# power_supply.net
KiCad netlist of a schematic drawn in Altium Designer
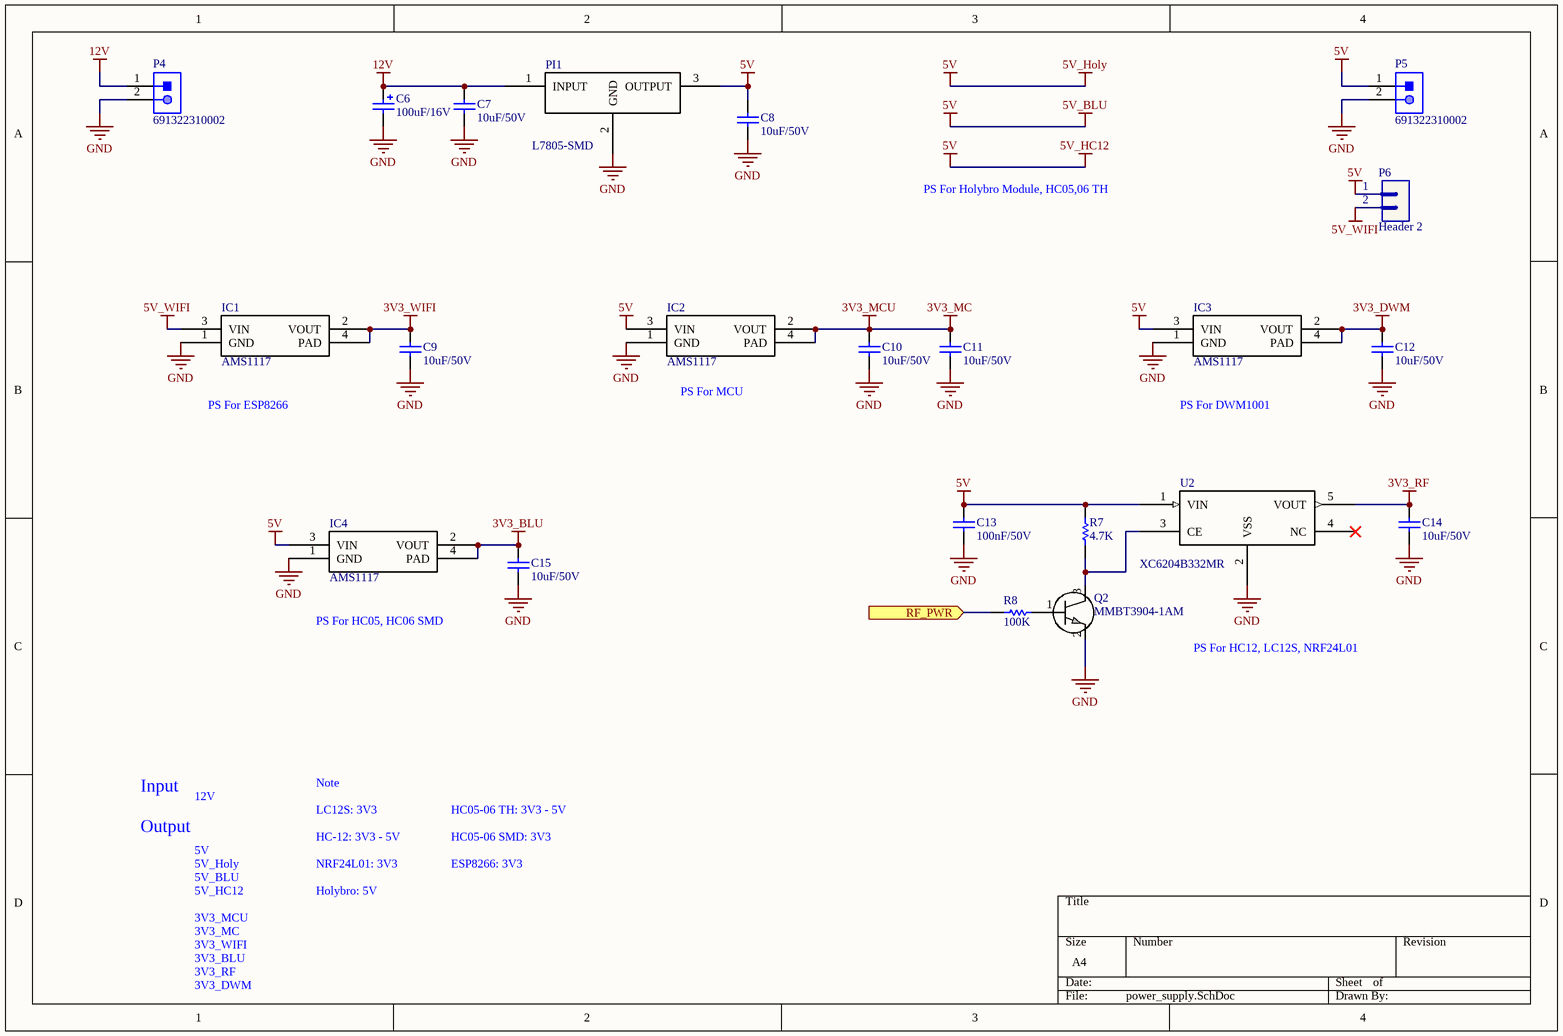
[diagram p0: power_supply.SchDoc]

(export (version "E")
  (design (tool "Eeschema 10.0.6"))
  (components
    (comp (ref "C6")
      (value "100uF/16V")
      (footprint "CAP-SM-AL-SIZE-D-D6L6")
      (description "CAP ALUM 100UF 20% 16V SMD")
      (fields
        (field (name "MANUFACTURER") "Nichicon")
        (field (name "MANUFACTURER PART NUMBER") "UWX1C101MCL1GB")
      )
      (libsource (lib "Capacitor") (part "Cap-Al-100uF-16V-D6L5"))
    )
    (comp (ref "C7")
      (value "10uF/50V")
      (footprint "CAP-SM-0805")
      (description "CAP CER 10UF 50V X5R 0805")
      (fields
        (field (name "MANUFACTURER") "Yageo")
        (field (name "MANUFACTURER PART NUMBER") "CC0805KKX5R9BB106")
      )
      (libsource (lib "Capacitor") (part "Cap-10uF-50V-0805"))
    )
    (comp (ref "C8")
      (value "10uF/50V")
      (footprint "CAP-SM-0805")
      (description "CAP CER 10UF 50V X5R 0805")
      (fields
        (field (name "MANUFACTURER") "Yageo")
        (field (name "MANUFACTURER PART NUMBER") "CC0805KKX5R9BB106")
      )
      (libsource (lib "Capacitor") (part "Cap-10uF-50V-0805"))
    )
    (comp (ref "C9")
      (value "10uF/50V")
      (footprint "CAP-SM-0805")
      (description "CAP CER 10UF 50V X5R 0805")
      (fields
        (field (name "MANUFACTURER") "Yageo")
        (field (name "MANUFACTURER PART NUMBER") "CC0805KKX5R9BB106")
      )
      (libsource (lib "Capacitor") (part "Cap-10uF-50V-0805"))
    )
    (comp (ref "C10")
      (value "10uF/50V")
      (footprint "CAP-SM-0805")
      (description "CAP CER 10UF 50V X5R 0805")
      (fields
        (field (name "MANUFACTURER") "Yageo")
        (field (name "MANUFACTURER PART NUMBER") "CC0805KKX5R9BB106")
      )
      (libsource (lib "Capacitor") (part "Cap-10uF-50V-0805"))
    )
    (comp (ref "C11")
      (value "10uF/50V")
      (footprint "CAP-SM-0805")
      (description "CAP CER 10UF 50V X5R 0805")
      (fields
        (field (name "MANUFACTURER") "Yageo")
        (field (name "MANUFACTURER PART NUMBER") "CC0805KKX5R9BB106")
      )
      (libsource (lib "Capacitor") (part "Cap-10uF-50V-0805"))
    )
    (comp (ref "C12")
      (value "10uF/50V")
      (footprint "CAP-SM-0805")
      (description "CAP CER 10UF 50V X5R 0805")
      (fields
        (field (name "MANUFACTURER") "Yageo")
        (field (name "MANUFACTURER PART NUMBER") "CC0805KKX5R9BB106")
      )
      (libsource (lib "Capacitor") (part "Cap-10uF-50V-0805"))
    )
    (comp (ref "C13")
      (value "100nF/50V")
      (footprint "CAP-SM-0805")
      (description "CAP CER 0.1UF 50V Y5V 0805")
      (fields
        (field (name "MANUFACTURER") "Samsung Electro-Mechanics")
        (field (name "MANUFACTURER PART NUMBER") "CL21F104ZBCNNNC")
      )
      (libsource (lib "Capacitor") (part "Cap-100nF-50V-0805"))
    )
    (comp (ref "C14")
      (value "10uF/50V")
      (footprint "CAP-SM-0805")
      (description "CAP CER 10UF 50V X5R 0805")
      (fields
        (field (name "MANUFACTURER") "Yageo")
        (field (name "MANUFACTURER PART NUMBER") "CC0805KKX5R9BB106")
      )
      (libsource (lib "Capacitor") (part "Cap-10uF-50V-0805"))
    )
    (comp (ref "C15")
      (value "10uF/50V")
      (footprint "CAP-SM-0805")
      (description "CAP CER 10UF 50V X5R 0805")
      (fields
        (field (name "MANUFACTURER") "Yageo")
        (field (name "MANUFACTURER PART NUMBER") "CC0805KKX5R9BB106")
      )
      (libsource (lib "Capacitor") (part "Cap-10uF-50V-0805"))
    )
    (comp (ref "IC1")
      (value "AMS1117")
      (footprint "SOT223_AMS111700")
      (fields
        (field (name "MANUFACTURER_PART_NUMBER") "AMS1117-5.0")
        (field (name "COPYRIGHT") "Copyright (C) 2018 Accelerated Designs. All rights reserved")
      )
      (libsource (lib "xecanbang") (part "AMS1117"))
    )
    (comp (ref "IC2")
      (value "AMS1117")
      (footprint "SOT223_AMS111700")
      (fields
        (field (name "MANUFACTURER_PART_NUMBER") "AMS1117-5.0")
        (field (name "COPYRIGHT") "Copyright (C) 2018 Accelerated Designs. All rights reserved")
      )
      (libsource (lib "xecanbang") (part "AMS1117"))
    )
    (comp (ref "IC3")
      (value "AMS1117")
      (footprint "SOT223_AMS111700")
      (fields
        (field (name "MANUFACTURER_PART_NUMBER") "AMS1117-5.0")
        (field (name "COPYRIGHT") "Copyright (C) 2018 Accelerated Designs. All rights reserved")
      )
      (libsource (lib "xecanbang") (part "AMS1117"))
    )
    (comp (ref "IC4")
      (value "AMS1117")
      (footprint "SOT223_AMS111700")
      (fields
        (field (name "MANUFACTURER_PART_NUMBER") "AMS1117-5.0")
        (field (name "COPYRIGHT") "Copyright (C) 2018 Accelerated Designs. All rights reserved")
      )
      (libsource (lib "xecanbang") (part "AMS1117"))
    )
    (comp (ref "P4")
      (value "691322310002")
      (footprint "691322310002")
      (description "WR-TBL Serie 322 Horizontal PCB Header, Pluggable, pitch 3.81mm, 2p")
      (fields (field (name "PUBLISHER") "Wurth Elektronik"))
      (libsource (lib "691322310002.") (part "691322310002"))
    )
    (comp (ref "P5")
      (value "691322310002")
      (footprint "691322310002")
      (description "WR-TBL Serie 322 Horizontal PCB Header, Pluggable, pitch 3.81mm, 2p")
      (fields (field (name "PUBLISHER") "Wurth Elektronik"))
      (libsource (lib "691322310002.") (part "691322310002"))
    )
    (comp (ref "P6")
      (value "Header 2")
      (footprint "JP2")
      (description "Header, 2-Pin")
      (fields (field (name "PUBLISHER") "Altium Limited"))
      (libsource (lib "Header-connector") (part "Header 2"))
    )
    (comp (ref "PI1")
      (value "L7805-SMD")
      (footprint "D2PAK")
      (fields
        (field (name "MANUFACTURER_PART_NUMBER") "L7805CD2T-TR")
        (field (name "COPYRIGHT") "Copyright (C) 2018 Accelerated Designs. All rights reserved")
      )
      (libsource (lib "xecanbang") (part "L7805-SMD"))
    )
    (comp (ref "Q2")
      (value "MMBT3904-1AM")
      (footprint "SOT23_NEX")
      (fields
        (field (name "MANUFACTURER_PART_NUMBER") "MMBT3904")
        (field (name "COPYRIGHT") "Copyright (C) 2016 Accelerated Designs. All rights reserved")
      )
      (libsource (lib "xecanbang") (part "MMBT3904-1AM"))
    )
    (comp (ref "R7")
      (value "4.7K")
      (footprint "Resistor:RES-SM-0805")
      (description "RES SMD 4.7K OHM 5% 1/8W 0805")
      (fields
        (field (name "MANUFACTURER") "Yageo")
        (field (name "MANUFACTURER PART NUMBER") "RC0805JR-074K7L")
      )
      (libsource (lib "Resistor") (part "Res-4.7K-0805"))
    )
    (comp (ref "R8")
      (value "100K")
      (footprint "Resistor:RES-SM-0805")
      (description "RES 0 OHM JUMPER 0805")
      (fields
        (field (name "MANUFACTURER") "Vishay Dale")
        (field (name "MANUFACTURER PART NUMBER") "WSL080500000ZEA9")
      )
      (libsource (lib "Resistor") (part "Res-100K-0805"))
    )
    (comp (ref "U2")
      (value "XC6204B332MR")
      (footprint "XC6204/05_SOT-25")
      (fields (field (name "COPYRIGHT") "Copyright (C) 2018 Accelerated Designs. All rights reserved"))
      (libsource (lib "xecanbang") (part "XC6204B332MR"))
    )
  )
  (nets
    (net (code "1") (name "/RF_PWR") (class "Default")
      (node (ref "R8") (pin "1") (pinfunction "1_1") (pintype "passive"))
    )
    (net (code "2") (name "3V3_BLU") (class "Default")
      (node (ref "C15") (pin "2") (pinfunction "2_2") (pintype "passive"))
      (node (ref "IC4") (pin "2") (pinfunction "VOUT_2") (pintype "passive"))
      (node (ref "IC4") (pin "4") (pinfunction "PAD_4") (pintype "passive"))
    )
    (net (code "3") (name "3V3_DWM") (class "Default")
      (node (ref "C12") (pin "2") (pinfunction "2_2") (pintype "passive"))
      (node (ref "IC3") (pin "2") (pinfunction "VOUT_2") (pintype "passive"))
      (node (ref "IC3") (pin "4") (pinfunction "PAD_4") (pintype "passive"))
    )
    (net (code "4") (name "3V3_MC") (class "Default")
      (node (ref "C10") (pin "2") (pinfunction "2_2") (pintype "passive"))
      (node (ref "C11") (pin "2") (pinfunction "2_2") (pintype "passive"))
      (node (ref "IC2") (pin "2") (pinfunction "VOUT_2") (pintype "passive"))
      (node (ref "IC2") (pin "4") (pinfunction "PAD_4") (pintype "passive"))
    )
    (net (code "5") (name "3V3_RF") (class "Default")
      (node (ref "C14") (pin "2") (pinfunction "2_2") (pintype "passive"))
      (node (ref "U2") (pin "5") (pinfunction "VOUT_5") (pintype "output"))
    )
    (net (code "6") (name "3V3_WIFI") (class "Default")
      (node (ref "C9") (pin "2") (pinfunction "2_2") (pintype "passive"))
      (node (ref "IC1") (pin "2") (pinfunction "VOUT_2") (pintype "passive"))
      (node (ref "IC1") (pin "4") (pinfunction "PAD_4") (pintype "passive"))
    )
    (net (code "7") (name "5V") (class "Default")
      (node (ref "C13") (pin "2") (pinfunction "2_2") (pintype "passive"))
      (node (ref "C8") (pin "2") (pinfunction "2_2") (pintype "passive"))
      (node (ref "IC2") (pin "3") (pinfunction "VIN_3") (pintype "passive"))
      (node (ref "IC3") (pin "3") (pinfunction "VIN_3") (pintype "passive"))
      (node (ref "IC4") (pin "3") (pinfunction "VIN_3") (pintype "passive"))
      (node (ref "P5") (pin "1") (pinfunction "1_1") (pintype "passive"))
      (node (ref "P6") (pin "1") (pinfunction "1_1") (pintype "passive"))
      (node (ref "PI1") (pin "3") (pinfunction "OUTPUT_3") (pintype "passive"))
      (node (ref "R7") (pin "2") (pinfunction "2_2") (pintype "passive"))
      (node (ref "U2") (pin "1") (pinfunction "VIN_1") (pintype "input"))
    )
    (net (code "8") (name "5V_WIFI") (class "Default")
      (node (ref "IC1") (pin "3") (pinfunction "VIN_3") (pintype "passive"))
      (node (ref "P6") (pin "2") (pinfunction "2_2") (pintype "passive"))
    )
    (net (code "9") (name "12V") (class "Default")
      (node (ref "C6") (pin "1") (pinfunction "1_1") (pintype "passive"))
      (node (ref "C7") (pin "2") (pinfunction "2_2") (pintype "passive"))
      (node (ref "P4") (pin "1") (pinfunction "1_1") (pintype "passive"))
      (node (ref "PI1") (pin "1") (pinfunction "INPUT_1") (pintype "passive"))
    )
    (net (code "10") (name "GND") (class "Default")
      (node (ref "C10") (pin "1") (pinfunction "1_1") (pintype "passive"))
      (node (ref "C11") (pin "1") (pinfunction "1_1") (pintype "passive"))
      (node (ref "C12") (pin "1") (pinfunction "1_1") (pintype "passive"))
      (node (ref "C13") (pin "1") (pinfunction "1_1") (pintype "passive"))
      (node (ref "C14") (pin "1") (pinfunction "1_1") (pintype "passive"))
      (node (ref "C15") (pin "1") (pinfunction "1_1") (pintype "passive"))
      (node (ref "C6") (pin "2") (pinfunction "2_2") (pintype "passive"))
      (node (ref "C7") (pin "1") (pinfunction "1_1") (pintype "passive"))
      (node (ref "C8") (pin "1") (pinfunction "1_1") (pintype "passive"))
      (node (ref "C9") (pin "1") (pinfunction "1_1") (pintype "passive"))
      (node (ref "IC1") (pin "1") (pinfunction "GND_1") (pintype "passive"))
      (node (ref "IC2") (pin "1") (pinfunction "GND_1") (pintype "passive"))
      (node (ref "IC3") (pin "1") (pinfunction "GND_1") (pintype "passive"))
      (node (ref "IC4") (pin "1") (pinfunction "GND_1") (pintype "passive"))
      (node (ref "P4") (pin "2") (pinfunction "2_2") (pintype "passive"))
      (node (ref "P5") (pin "2") (pinfunction "2_2") (pintype "passive"))
      (node (ref "PI1") (pin "2") (pinfunction "GND_2") (pintype "passive"))
      (node (ref "Q2") (pin "2") (pinfunction "2_2") (pintype "passive"))
      (node (ref "U2") (pin "2") (pinfunction "VSS_2") (pintype "passive"))
    )
    (net (code "11") (name "Net-(Q2-Pad1)") (class "Default")
      (node (ref "Q2") (pin "1") (pinfunction "1_1") (pintype "passive"))
      (node (ref "R8") (pin "2") (pinfunction "2_2") (pintype "passive"))
    )
    (net (code "12") (name "Net-(U2-CE)") (class "Default")
      (node (ref "Q2") (pin "3") (pinfunction "3_3") (pintype "passive"))
      (node (ref "R7") (pin "1") (pinfunction "1_1") (pintype "passive"))
      (node (ref "U2") (pin "3") (pinfunction "CE_3") (pintype "passive"))
    )
    (net (code "13") (name "unconnected-(U2-NC-Pad4)") (class "Default")
      (node (ref "U2") (pin "4") (pinfunction "NC_4") (pintype "passive+no_connect"))
    )
  )
)
